# Torsteuerung_1_0.net
KiCad netlist of a schematic drawn in EAGLE
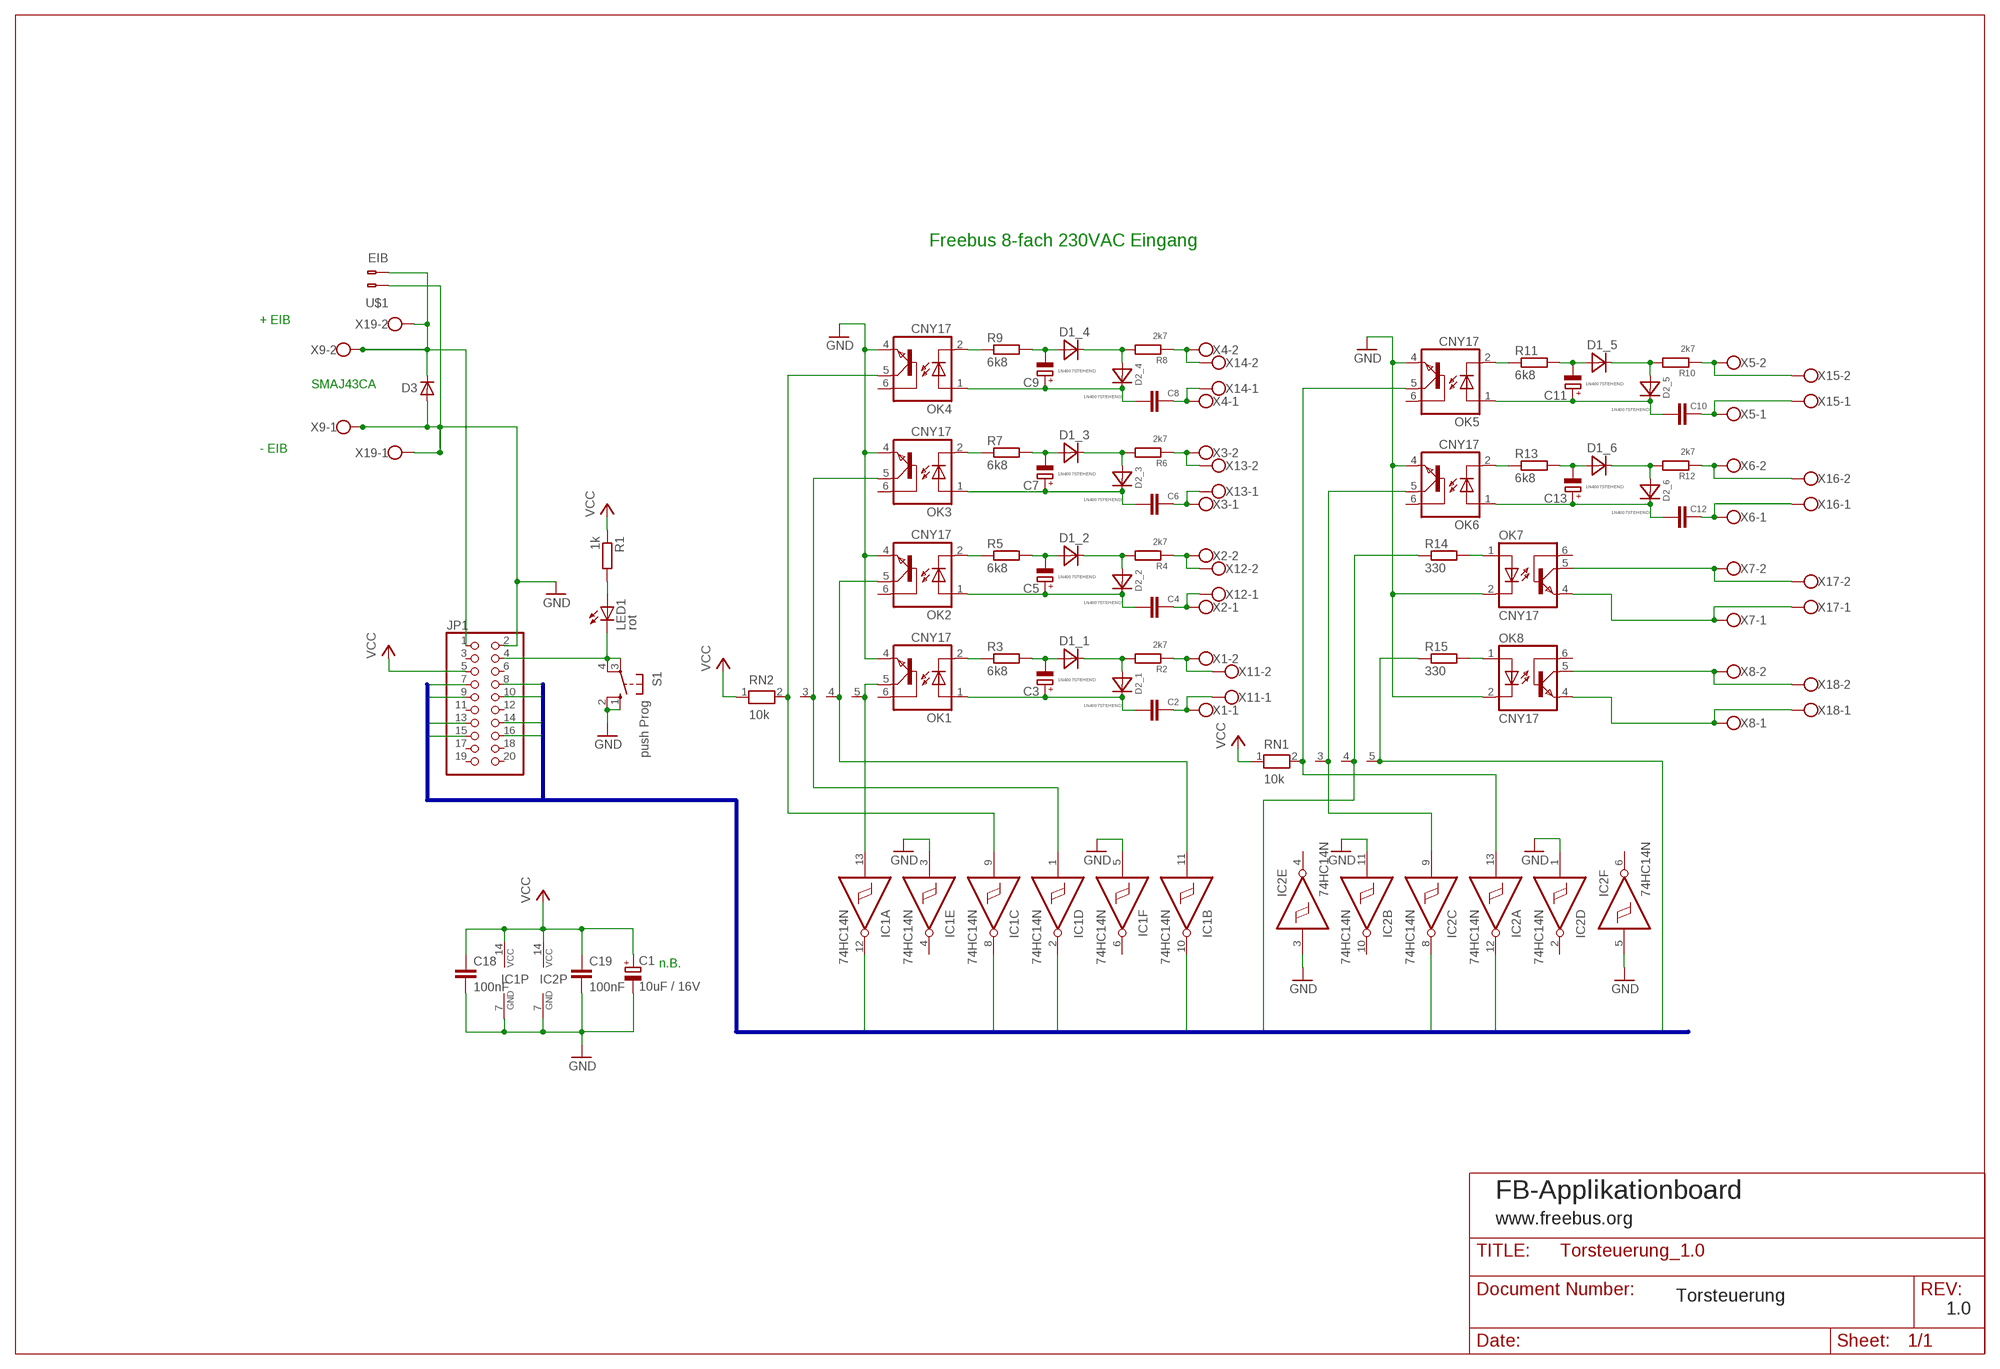
[diagram p0: schematic, sheet 1]

(export (version "E")
  (design (tool "Eeschema 10.0.6"))
  (components
    (comp (ref "C1")
      (value "10uF / 16V")
      (footprint "eagle-import:E2-4")
      (libsource (lib "eagle-import") (part "CPOL-EUE2-4"))
    )
    (comp (ref "C2")
      (value "C-EU075-063X106")
      (footprint "eagle-import:C075-063X106")
      (libsource (lib "eagle-import") (part "C-EU075-063X106"))
    )
    (comp (ref "C3")
      (value "CPOL-EUE2-4")
      (footprint "eagle-import:E2-4")
      (libsource (lib "eagle-import") (part "CPOL-EUE2-4"))
    )
    (comp (ref "C4")
      (value "C-EU075-063X106")
      (footprint "eagle-import:C075-063X106")
      (libsource (lib "eagle-import") (part "C-EU075-063X106"))
    )
    (comp (ref "C5")
      (value "CPOL-EUE2-4")
      (footprint "eagle-import:E2-4")
      (libsource (lib "eagle-import") (part "CPOL-EUE2-4"))
    )
    (comp (ref "C6")
      (value "C-EU075-063X106")
      (footprint "eagle-import:C075-063X106")
      (libsource (lib "eagle-import") (part "C-EU075-063X106"))
    )
    (comp (ref "C7")
      (value "CPOL-EUE2-4")
      (footprint "eagle-import:E2-4")
      (libsource (lib "eagle-import") (part "CPOL-EUE2-4"))
    )
    (comp (ref "C8")
      (value "C-EU075-063X106")
      (footprint "eagle-import:C075-063X106")
      (libsource (lib "eagle-import") (part "C-EU075-063X106"))
    )
    (comp (ref "C9")
      (value "CPOL-EUE2-4")
      (footprint "eagle-import:E2-4")
      (libsource (lib "eagle-import") (part "CPOL-EUE2-4"))
    )
    (comp (ref "C10")
      (value "C-EU075-063X106")
      (footprint "eagle-import:C075-063X106")
      (libsource (lib "eagle-import") (part "C-EU075-063X106"))
    )
    (comp (ref "C11")
      (value "CPOL-EUE2-4")
      (footprint "eagle-import:E2-4")
      (libsource (lib "eagle-import") (part "CPOL-EUE2-4"))
    )
    (comp (ref "C12")
      (value "C-EU075-063X106")
      (footprint "eagle-import:C075-063X106")
      (libsource (lib "eagle-import") (part "C-EU075-063X106"))
    )
    (comp (ref "C13")
      (value "CPOL-EUE2-4")
      (footprint "eagle-import:E2-4")
      (libsource (lib "eagle-import") (part "CPOL-EUE2-4"))
    )
    (comp (ref "C18")
      (value "100nF")
      (footprint "eagle-import:C050-024X044")
      (libsource (lib "eagle-import") (part "C-EU050-024X044"))
    )
    (comp (ref "C19")
      (value "100nF")
      (footprint "eagle-import:C050-024X044")
      (libsource (lib "eagle-import") (part "C-EU050-024X044"))
    )
    (comp (ref "D1_1")
      (value "1N4007STEHEND")
      (footprint "eagle-import:RAD2,5")
      (libsource (lib "eagle-import") (part "1N4007STEHEND"))
    )
    (comp (ref "D1_2")
      (value "1N4007STEHEND")
      (footprint "eagle-import:RAD2,5")
      (libsource (lib "eagle-import") (part "1N4007STEHEND"))
    )
    (comp (ref "D1_3")
      (value "1N4007STEHEND")
      (footprint "eagle-import:RAD2,5")
      (libsource (lib "eagle-import") (part "1N4007STEHEND"))
    )
    (comp (ref "D1_4")
      (value "1N4007STEHEND")
      (footprint "eagle-import:RAD2,5")
      (libsource (lib "eagle-import") (part "1N4007STEHEND"))
    )
    (comp (ref "D1_5")
      (value "1N4007STEHEND")
      (footprint "eagle-import:RAD2,5")
      (libsource (lib "eagle-import") (part "1N4007STEHEND"))
    )
    (comp (ref "D1_6")
      (value "1N4007STEHEND")
      (footprint "eagle-import:RAD2,5")
      (libsource (lib "eagle-import") (part "1N4007STEHEND"))
    )
    (comp (ref "D2_1")
      (value "1N4007STEHEND")
      (footprint "eagle-import:RAD2,5")
      (libsource (lib "eagle-import") (part "1N4007STEHEND"))
    )
    (comp (ref "D2_2")
      (value "1N4007STEHEND")
      (footprint "eagle-import:RAD2,5")
      (libsource (lib "eagle-import") (part "1N4007STEHEND"))
    )
    (comp (ref "D2_3")
      (value "1N4007STEHEND")
      (footprint "eagle-import:RAD2,5")
      (libsource (lib "eagle-import") (part "1N4007STEHEND"))
    )
    (comp (ref "D2_4")
      (value "1N4007STEHEND")
      (footprint "eagle-import:RAD2,5")
      (libsource (lib "eagle-import") (part "1N4007STEHEND"))
    )
    (comp (ref "D2_5")
      (value "1N4007STEHEND")
      (footprint "eagle-import:RAD2,5")
      (libsource (lib "eagle-import") (part "1N4007STEHEND"))
    )
    (comp (ref "D2_6")
      (value "1N4007STEHEND")
      (footprint "eagle-import:RAD2,5")
      (libsource (lib "eagle-import") (part "1N4007STEHEND"))
    )
    (comp (ref "D3")
      (value "D-SMB")
      (footprint "eagle-import:SMB")
      (libsource (lib "eagle-import") (part "D-SMB"))
    )
    (comp (ref "IC1")
      (value "74HC14N")
      (footprint "eagle-import:DIL14")
      (libsource (lib "eagle-import") (part "7414NHC"))
    )
    (comp (ref "IC2")
      (value "74HC14N")
      (footprint "eagle-import:DIL14")
      (libsource (lib "eagle-import") (part "7414NHC"))
    )
    (comp (ref "JP1")
      (value "PINHD-2X10")
      (footprint "eagle-import:2X10")
      (libsource (lib "eagle-import") (part "PINHD-2X10"))
    )
    (comp (ref "LED1")
      (value "rot")
      (footprint "eagle-import:LED3MM")
      (libsource (lib "eagle-import") (part "LED3MM"))
    )
    (comp (ref "OK1")
      (value "CNY17")
      (footprint "eagle-import:DIL06")
      (libsource (lib "eagle-import") (part "CNY17"))
    )
    (comp (ref "OK2")
      (value "CNY17")
      (footprint "eagle-import:DIL06")
      (libsource (lib "eagle-import") (part "CNY17"))
    )
    (comp (ref "OK3")
      (value "CNY17")
      (footprint "eagle-import:DIL06")
      (libsource (lib "eagle-import") (part "CNY17"))
    )
    (comp (ref "OK4")
      (value "CNY17")
      (footprint "eagle-import:DIL06")
      (libsource (lib "eagle-import") (part "CNY17"))
    )
    (comp (ref "OK5")
      (value "CNY17")
      (footprint "eagle-import:DIL06")
      (libsource (lib "eagle-import") (part "CNY17"))
    )
    (comp (ref "OK6")
      (value "CNY17")
      (footprint "eagle-import:DIL06")
      (libsource (lib "eagle-import") (part "CNY17"))
    )
    (comp (ref "OK7")
      (value "CNY17")
      (footprint "eagle-import:DIL06")
      (libsource (lib "eagle-import") (part "CNY17"))
    )
    (comp (ref "OK8")
      (value "CNY17")
      (footprint "eagle-import:DIL06")
      (libsource (lib "eagle-import") (part "CNY17"))
    )
    (comp (ref "R1")
      (value "1k")
      (footprint "eagle-import:0204_7")
      (libsource (lib "eagle-import") (part "R-EU_0204/7"))
    )
    (comp (ref "R2")
      (value "2k7")
      (footprint "eagle-import:0207_2V")
      (libsource (lib "eagle-import") (part "R-EU_0207/2V"))
    )
    (comp (ref "R3")
      (value "6k8")
      (footprint "eagle-import:0207_2V")
      (libsource (lib "eagle-import") (part "R-EU_0207/2V"))
    )
    (comp (ref "R4")
      (value "2k7")
      (footprint "eagle-import:0207_2V")
      (libsource (lib "eagle-import") (part "R-EU_0207/2V"))
    )
    (comp (ref "R5")
      (value "6k8")
      (footprint "eagle-import:0207_2V")
      (libsource (lib "eagle-import") (part "R-EU_0207/2V"))
    )
    (comp (ref "R6")
      (value "2k7")
      (footprint "eagle-import:0207_2V")
      (libsource (lib "eagle-import") (part "R-EU_0207/2V"))
    )
    (comp (ref "R7")
      (value "6k8")
      (footprint "eagle-import:0207_2V")
      (libsource (lib "eagle-import") (part "R-EU_0207/2V"))
    )
    (comp (ref "R8")
      (value "2k7")
      (footprint "eagle-import:0207_2V")
      (libsource (lib "eagle-import") (part "R-EU_0207/2V"))
    )
    (comp (ref "R9")
      (value "6k8")
      (footprint "eagle-import:0207_2V")
      (libsource (lib "eagle-import") (part "R-EU_0207/2V"))
    )
    (comp (ref "R10")
      (value "2k7")
      (footprint "eagle-import:0207_2V")
      (libsource (lib "eagle-import") (part "R-EU_0207/2V"))
    )
    (comp (ref "R11")
      (value "6k8")
      (footprint "eagle-import:0207_2V")
      (libsource (lib "eagle-import") (part "R-EU_0207/2V"))
    )
    (comp (ref "R12")
      (value "2k7")
      (footprint "eagle-import:0207_2V")
      (libsource (lib "eagle-import") (part "R-EU_0207/2V"))
    )
    (comp (ref "R13")
      (value "6k8")
      (footprint "eagle-import:0207_2V")
      (libsource (lib "eagle-import") (part "R-EU_0207/2V"))
    )
    (comp (ref "R14")
      (value "330")
      (footprint "eagle-import:0204_5")
      (libsource (lib "eagle-import") (part "R-EU_0204/5"))
    )
    (comp (ref "R15")
      (value "330")
      (footprint "eagle-import:0204_5")
      (libsource (lib "eagle-import") (part "R-EU_0204/5"))
    )
    (comp (ref "RN1")
      (value "10k")
      (footprint "eagle-import:RN-5")
      (libsource (lib "eagle-import") (part "RN04"))
    )
    (comp (ref "RN2")
      (value "10k")
      (footprint "eagle-import:RN-5")
      (libsource (lib "eagle-import") (part "RN04"))
    )
    (comp (ref "S1")
      (value "push Prog")
      (footprint "eagle-import:B3F-10XX")
      (libsource (lib "eagle-import") (part "10-XX"))
    )
    (comp (ref "U$1")
      (value "EIB")
      (footprint "eagle-import:BUSKLEMME243-724")
      (libsource (lib "eagle-import") (part "EIB"))
    )
    (comp (ref "X1")
      (value "W237-102")
      (footprint "eagle-import:W237-102")
      (libsource (lib "eagle-import") (part "W237-102"))
    )
    (comp (ref "X2")
      (value "W237-102")
      (footprint "eagle-import:W237-102")
      (libsource (lib "eagle-import") (part "W237-102"))
    )
    (comp (ref "X3")
      (value "W237-102")
      (footprint "eagle-import:W237-102")
      (libsource (lib "eagle-import") (part "W237-102"))
    )
    (comp (ref "X4")
      (value "W237-102")
      (footprint "eagle-import:W237-102")
      (libsource (lib "eagle-import") (part "W237-102"))
    )
    (comp (ref "X5")
      (value "W237-102")
      (footprint "eagle-import:W237-102")
      (libsource (lib "eagle-import") (part "W237-102"))
    )
    (comp (ref "X6")
      (value "W237-102")
      (footprint "eagle-import:W237-102")
      (libsource (lib "eagle-import") (part "W237-102"))
    )
    (comp (ref "X7")
      (value "W237-102")
      (footprint "eagle-import:W237-102")
      (libsource (lib "eagle-import") (part "W237-102"))
    )
    (comp (ref "X8")
      (value "W237-102")
      (footprint "eagle-import:W237-102")
      (libsource (lib "eagle-import") (part "W237-102"))
    )
    (comp (ref "X9")
      (value "W237-102")
      (footprint "eagle-import:W237-102")
      (libsource (lib "eagle-import") (part "W237-102"))
    )
    (comp (ref "X11")
      (value "W237-102AKL007-2P")
      (footprint "eagle-import:AKL007-02")
      (libsource (lib "eagle-import") (part "W237-102AKL007-2P"))
    )
    (comp (ref "X12")
      (value "W237-102AKL007-2P")
      (footprint "eagle-import:AKL007-02")
      (libsource (lib "eagle-import") (part "W237-102AKL007-2P"))
    )
    (comp (ref "X13")
      (value "W237-102AKL007-2P")
      (footprint "eagle-import:AKL007-02")
      (libsource (lib "eagle-import") (part "W237-102AKL007-2P"))
    )
    (comp (ref "X14")
      (value "W237-102AKL007-2P")
      (footprint "eagle-import:AKL007-02")
      (libsource (lib "eagle-import") (part "W237-102AKL007-2P"))
    )
    (comp (ref "X15")
      (value "W237-102AKL007-2P")
      (footprint "eagle-import:AKL007-02")
      (libsource (lib "eagle-import") (part "W237-102AKL007-2P"))
    )
    (comp (ref "X16")
      (value "W237-102AKL007-2P")
      (footprint "eagle-import:AKL007-02")
      (libsource (lib "eagle-import") (part "W237-102AKL007-2P"))
    )
    (comp (ref "X17")
      (value "W237-102AKL007-2P")
      (footprint "eagle-import:AKL007-02")
      (libsource (lib "eagle-import") (part "W237-102AKL007-2P"))
    )
    (comp (ref "X18")
      (value "W237-102AKL007-2P")
      (footprint "eagle-import:AKL007-02")
      (libsource (lib "eagle-import") (part "W237-102AKL007-2P"))
    )
    (comp (ref "X19")
      (value "W237-102AKL007-2P")
      (footprint "eagle-import:AKL007-02")
      (libsource (lib "eagle-import") (part "W237-102AKL007-2P"))
    )
  )
  (nets
    (net (code "1") (name "/IO1") (class "Default")
      (node (ref "IC1") (pin "12") (pinfunction "O_12") (pintype "output"))
      (node (ref "JP1") (pin "7") (pinfunction "7_7") (pintype "passive"))
    )
    (net (code "2") (name "/IO2") (class "Default")
      (node (ref "IC1") (pin "10") (pinfunction "O_10") (pintype "output"))
      (node (ref "JP1") (pin "8") (pinfunction "8_8") (pintype "passive"))
    )
    (net (code "3") (name "/IO3") (class "Default")
      (node (ref "IC1") (pin "2") (pinfunction "O_2") (pintype "output"))
      (node (ref "JP1") (pin "9") (pinfunction "9_9") (pintype "passive"))
    )
    (net (code "4") (name "/IO4") (class "Default")
      (node (ref "IC1") (pin "8") (pinfunction "O_8") (pintype "output"))
      (node (ref "JP1") (pin "10") (pinfunction "10_10") (pintype "passive"))
    )
    (net (code "5") (name "/IO5") (class "Default")
      (node (ref "IC2") (pin "12") (pinfunction "O_12") (pintype "output"))
      (node (ref "JP1") (pin "13") (pinfunction "13_13") (pintype "passive"))
    )
    (net (code "6") (name "/IO6") (class "Default")
      (node (ref "IC2") (pin "8") (pinfunction "O_8") (pintype "output"))
      (node (ref "JP1") (pin "14") (pinfunction "14_14") (pintype "passive"))
    )
    (net (code "7") (name "/IO7") (class "Default")
      (node (ref "JP1") (pin "15") (pinfunction "15_15") (pintype "passive"))
      (node (ref "R14") (pin "1") (pinfunction "1_1") (pintype "passive"))
      (node (ref "RN1") (pin "4") (pinfunction "4_4") (pintype "passive"))
    )
    (net (code "8") (name "/IO8") (class "Default")
      (node (ref "JP1") (pin "16") (pinfunction "16_16") (pintype "passive"))
      (node (ref "R15") (pin "1") (pinfunction "1_1") (pintype "passive"))
      (node (ref "RN1") (pin "5") (pinfunction "5_5") (pintype "passive"))
    )
    (net (code "9") (name "GND") (class "Default")
      (node (ref "C1") (pin "-") (pinfunction "-_-") (pintype "passive"))
      (node (ref "C18") (pin "2") (pinfunction "2_2") (pintype "passive"))
      (node (ref "C19") (pin "2") (pinfunction "2_2") (pintype "passive"))
      (node (ref "D3") (pin "2") (pinfunction "A_2") (pintype "passive"))
      (node (ref "IC1") (pin "3") (pinfunction "I_3") (pintype "input"))
      (node (ref "IC1") (pin "5") (pinfunction "I_5") (pintype "input"))
      (node (ref "IC1") (pin "7") (pinfunction "GND_7") (pintype "power_in"))
      (node (ref "IC2") (pin "1") (pinfunction "I_1") (pintype "input"))
      (node (ref "IC2") (pin "11") (pinfunction "I_11") (pintype "input"))
      (node (ref "IC2") (pin "3") (pinfunction "I_3") (pintype "input"))
      (node (ref "IC2") (pin "5") (pinfunction "I_5") (pintype "input"))
      (node (ref "IC2") (pin "7") (pinfunction "GND_7") (pintype "power_in"))
      (node (ref "JP1") (pin "2") (pinfunction "2_2") (pintype "passive"))
      (node (ref "OK1") (pin "4") (pinfunction "EMI_4") (pintype "passive"))
      (node (ref "OK2") (pin "4") (pinfunction "EMI_4") (pintype "passive"))
      (node (ref "OK3") (pin "4") (pinfunction "EMI_4") (pintype "passive"))
      (node (ref "OK4") (pin "4") (pinfunction "EMI_4") (pintype "passive"))
      (node (ref "OK5") (pin "4") (pinfunction "EMI_4") (pintype "passive"))
      (node (ref "OK6") (pin "4") (pinfunction "EMI_4") (pintype "passive"))
      (node (ref "OK7") (pin "2") (pinfunction "C_2") (pintype "passive"))
      (node (ref "OK8") (pin "2") (pinfunction "C_2") (pintype "passive"))
      (node (ref "S1") (pin "1") (pinfunction "S_1") (pintype "passive"))
      (node (ref "S1") (pin "2") (pinfunction "S1_2") (pintype "passive"))
      (node (ref "U$1") (pin "1") (pinfunction "B-1_1") (pintype "passive"))
      (node (ref "X19") (pin "1") (pinfunction "KL_1") (pintype "passive"))
      (node (ref "X9") (pin "1") (pinfunction "KL_1") (pintype "passive"))
    )
    (net (code "10") (name "Net-(C3-Pad-)") (class "Default")
      (node (ref "C3") (pin "-") (pinfunction "-_-") (pintype "passive"))
      (node (ref "D1_1") (pin "A") (pinfunction "A_A") (pintype "passive"))
      (node (ref "R3") (pin "2") (pinfunction "2_2") (pintype "passive"))
    )
    (net (code "11") (name "Net-(C5-Pad-)") (class "Default")
      (node (ref "C5") (pin "-") (pinfunction "-_-") (pintype "passive"))
      (node (ref "D1_2") (pin "A") (pinfunction "A_A") (pintype "passive"))
      (node (ref "R5") (pin "2") (pinfunction "2_2") (pintype "passive"))
    )
    (net (code "12") (name "Net-(C7-Pad-)") (class "Default")
      (node (ref "C7") (pin "-") (pinfunction "-_-") (pintype "passive"))
      (node (ref "D1_3") (pin "A") (pinfunction "A_A") (pintype "passive"))
      (node (ref "R7") (pin "2") (pinfunction "2_2") (pintype "passive"))
    )
    (net (code "13") (name "Net-(C9-Pad-)") (class "Default")
      (node (ref "C9") (pin "-") (pinfunction "-_-") (pintype "passive"))
      (node (ref "D1_4") (pin "A") (pinfunction "A_A") (pintype "passive"))
      (node (ref "R9") (pin "2") (pinfunction "2_2") (pintype "passive"))
    )
    (net (code "14") (name "Net-(C11-Pad-)") (class "Default")
      (node (ref "C11") (pin "-") (pinfunction "-_-") (pintype "passive"))
      (node (ref "D1_5") (pin "A") (pinfunction "A_A") (pintype "passive"))
      (node (ref "R11") (pin "2") (pinfunction "2_2") (pintype "passive"))
    )
    (net (code "15") (name "Net-(C13-Pad-)") (class "Default")
      (node (ref "C13") (pin "-") (pinfunction "-_-") (pintype "passive"))
      (node (ref "D1_6") (pin "A") (pinfunction "A_A") (pintype "passive"))
      (node (ref "R13") (pin "2") (pinfunction "2_2") (pintype "passive"))
    )
    (net (code "16") (name "Net-(D1_1-PadC)") (class "Default")
      (node (ref "D1_1") (pin "C") (pinfunction "C_C") (pintype "passive"))
      (node (ref "D2_1") (pin "A") (pinfunction "A_A") (pintype "passive"))
      (node (ref "R2") (pin "2") (pinfunction "2_2") (pintype "passive"))
    )
    (net (code "17") (name "Net-(D1_2-PadC)") (class "Default")
      (node (ref "D1_2") (pin "C") (pinfunction "C_C") (pintype "passive"))
      (node (ref "D2_2") (pin "A") (pinfunction "A_A") (pintype "passive"))
      (node (ref "R4") (pin "2") (pinfunction "2_2") (pintype "passive"))
    )
    (net (code "18") (name "Net-(D1_3-PadC)") (class "Default")
      (node (ref "D1_3") (pin "C") (pinfunction "C_C") (pintype "passive"))
      (node (ref "D2_3") (pin "A") (pinfunction "A_A") (pintype "passive"))
      (node (ref "R6") (pin "2") (pinfunction "2_2") (pintype "passive"))
    )
    (net (code "19") (name "Net-(D1_4-PadC)") (class "Default")
      (node (ref "D1_4") (pin "C") (pinfunction "C_C") (pintype "passive"))
      (node (ref "D2_4") (pin "A") (pinfunction "A_A") (pintype "passive"))
      (node (ref "R8") (pin "2") (pinfunction "2_2") (pintype "passive"))
    )
    (net (code "20") (name "Net-(D1_5-PadC)") (class "Default")
      (node (ref "D1_5") (pin "C") (pinfunction "C_C") (pintype "passive"))
      (node (ref "D2_5") (pin "A") (pinfunction "A_A") (pintype "passive"))
      (node (ref "R10") (pin "2") (pinfunction "2_2") (pintype "passive"))
    )
    (net (code "21") (name "Net-(D1_6-PadC)") (class "Default")
      (node (ref "D1_6") (pin "C") (pinfunction "C_C") (pintype "passive"))
      (node (ref "D2_6") (pin "A") (pinfunction "A_A") (pintype "passive"))
      (node (ref "R12") (pin "2") (pinfunction "2_2") (pintype "passive"))
    )
    (net (code "22") (name "Net-(D3-C)") (class "Default")
      (node (ref "D3") (pin "1") (pinfunction "C_1") (pintype "passive"))
      (node (ref "JP1") (pin "1") (pinfunction "1_1") (pintype "passive"))
      (node (ref "U$1") (pin "2") (pinfunction "B-2_2") (pintype "passive"))
      (node (ref "X19") (pin "2") (pinfunction "KL_2") (pintype "passive"))
      (node (ref "X9") (pin "2") (pinfunction "KL_2") (pintype "passive"))
    )
    (net (code "23") (name "Net-(IC1A-I)") (class "Default")
      (node (ref "IC1") (pin "13") (pinfunction "I_13") (pintype "input"))
      (node (ref "OK1") (pin "5") (pinfunction "COL_5") (pintype "passive"))
      (node (ref "RN2") (pin "5") (pinfunction "5_5") (pintype "passive"))
    )
    (net (code "24") (name "Net-(IC1B-I)") (class "Default")
      (node (ref "IC1") (pin "11") (pinfunction "I_11") (pintype "input"))
      (node (ref "OK2") (pin "5") (pinfunction "COL_5") (pintype "passive"))
      (node (ref "RN2") (pin "4") (pinfunction "4_4") (pintype "passive"))
    )
    (net (code "25") (name "Net-(IC1C-I)") (class "Default")
      (node (ref "IC1") (pin "9") (pinfunction "I_9") (pintype "input"))
      (node (ref "OK4") (pin "5") (pinfunction "COL_5") (pintype "passive"))
      (node (ref "RN2") (pin "2") (pinfunction "2_2") (pintype "passive"))
    )
    (net (code "26") (name "Net-(IC1D-I)") (class "Default")
      (node (ref "IC1") (pin "1") (pinfunction "I_1") (pintype "input"))
      (node (ref "OK3") (pin "5") (pinfunction "COL_5") (pintype "passive"))
      (node (ref "RN2") (pin "3") (pinfunction "3_3") (pintype "passive"))
    )
    (net (code "27") (name "Net-(IC2A-I)") (class "Default")
      (node (ref "IC2") (pin "13") (pinfunction "I_13") (pintype "input"))
      (node (ref "OK5") (pin "5") (pinfunction "COL_5") (pintype "passive"))
      (node (ref "RN1") (pin "2") (pinfunction "2_2") (pintype "passive"))
    )
    (net (code "28") (name "Net-(IC2C-I)") (class "Default")
      (node (ref "IC2") (pin "9") (pinfunction "I_9") (pintype "input"))
      (node (ref "OK6") (pin "5") (pinfunction "COL_5") (pintype "passive"))
      (node (ref "RN1") (pin "3") (pinfunction "3_3") (pintype "passive"))
    )
    (net (code "29") (name "Net-(LED1-C)") (class "Default")
      (node (ref "JP1") (pin "4") (pinfunction "4_4") (pintype "passive"))
      (node (ref "LED1") (pin "K") (pinfunction "C_K") (pintype "passive"))
      (node (ref "S1") (pin "3") (pinfunction "P_3") (pintype "passive"))
      (node (ref "S1") (pin "4") (pinfunction "P1_4") (pintype "passive"))
    )
    (net (code "30") (name "Net-(LED1-PadA)") (class "Default")
      (node (ref "LED1") (pin "A") (pinfunction "A_A") (pintype "passive"))
      (node (ref "R1") (pin "2") (pinfunction "2_2") (pintype "passive"))
    )
    (net (code "31") (name "Net-(OK1-A)") (class "Default")
      (node (ref "C2") (pin "1") (pinfunction "1_1") (pintype "passive"))
      (node (ref "C3") (pin "+") (pinfunction "+_+") (pintype "passive"))
      (node (ref "D2_1") (pin "C") (pinfunction "C_C") (pintype "passive"))
      (node (ref "OK1") (pin "1") (pinfunction "A_1") (pintype "passive"))
    )
    (net (code "32") (name "Net-(OK1-C)") (class "Default")
      (node (ref "OK1") (pin "2") (pinfunction "C_2") (pintype "passive"))
      (node (ref "R3") (pin "1") (pinfunction "1_1") (pintype "passive"))
    )
    (net (code "33") (name "Net-(OK2-A)") (class "Default")
      (node (ref "C4") (pin "1") (pinfunction "1_1") (pintype "passive"))
      (node (ref "C5") (pin "+") (pinfunction "+_+") (pintype "passive"))
      (node (ref "D2_2") (pin "C") (pinfunction "C_C") (pintype "passive"))
      (node (ref "OK2") (pin "1") (pinfunction "A_1") (pintype "passive"))
    )
    (net (code "34") (name "Net-(OK2-C)") (class "Default")
      (node (ref "OK2") (pin "2") (pinfunction "C_2") (pintype "passive"))
      (node (ref "R5") (pin "1") (pinfunction "1_1") (pintype "passive"))
    )
    (net (code "35") (name "Net-(OK3-A)") (class "Default")
      (node (ref "C6") (pin "1") (pinfunction "1_1") (pintype "passive"))
      (node (ref "C7") (pin "+") (pinfunction "+_+") (pintype "passive"))
      (node (ref "D2_3") (pin "C") (pinfunction "C_C") (pintype "passive"))
      (node (ref "OK3") (pin "1") (pinfunction "A_1") (pintype "passive"))
    )
    (net (code "36") (name "Net-(OK3-C)") (class "Default")
      (node (ref "OK3") (pin "2") (pinfunction "C_2") (pintype "passive"))
      (node (ref "R7") (pin "1") (pinfunction "1_1") (pintype "passive"))
    )
    (net (code "37") (name "Net-(OK4-A)") (class "Default")
      (node (ref "C8") (pin "1") (pinfunction "1_1") (pintype "passive"))
      (node (ref "C9") (pin "+") (pinfunction "+_+") (pintype "passive"))
      (node (ref "D2_4") (pin "C") (pinfunction "C_C") (pintype "passive"))
      (node (ref "OK4") (pin "1") (pinfunction "A_1") (pintype "passive"))
    )
    (net (code "38") (name "Net-(OK4-C)") (class "Default")
      (node (ref "OK4") (pin "2") (pinfunction "C_2") (pintype "passive"))
      (node (ref "R9") (pin "1") (pinfunction "1_1") (pintype "passive"))
    )
    (net (code "39") (name "Net-(OK5-A)") (class "Default")
      (node (ref "C10") (pin "1") (pinfunction "1_1") (pintype "passive"))
      (node (ref "C11") (pin "+") (pinfunction "+_+") (pintype "passive"))
      (node (ref "D2_5") (pin "C") (pinfunction "C_C") (pintype "passive"))
      (node (ref "OK5") (pin "1") (pinfunction "A_1") (pintype "passive"))
    )
    (net (code "40") (name "Net-(OK5-C)") (class "Default")
      (node (ref "OK5") (pin "2") (pinfunction "C_2") (pintype "passive"))
      (node (ref "R11") (pin "1") (pinfunction "1_1") (pintype "passive"))
    )
    (net (code "41") (name "Net-(OK6-A)") (class "Default")
      (node (ref "C12") (pin "1") (pinfunction "1_1") (pintype "passive"))
      (node (ref "C13") (pin "+") (pinfunction "+_+") (pintype "passive"))
      (node (ref "D2_6") (pin "C") (pinfunction "C_C") (pintype "passive"))
      (node (ref "OK6") (pin "1") (pinfunction "A_1") (pintype "passive"))
    )
    (net (code "42") (name "Net-(OK6-C)") (class "Default")
      (node (ref "OK6") (pin "2") (pinfunction "C_2") (pintype "passive"))
      (node (ref "R13") (pin "1") (pinfunction "1_1") (pintype "passive"))
    )
    (net (code "43") (name "Net-(OK7-A)") (class "Default")
      (node (ref "OK7") (pin "1") (pinfunction "A_1") (pintype "passive"))
      (node (ref "R14") (pin "2") (pinfunction "2_2") (pintype "passive"))
    )
    (net (code "44") (name "Net-(OK7-COL)") (class "Default")
      (node (ref "OK7") (pin "5") (pinfunction "COL_5") (pintype "passive"))
      (node (ref "X17") (pin "2") (pinfunction "KL_2") (pintype "passive"))
      (node (ref "X7") (pin "2") (pinfunction "KL_2") (pintype "passive"))
    )
    (net (code "45") (name "Net-(OK7-EMI)") (class "Default")
      (node (ref "OK7") (pin "4") (pinfunction "EMI_4") (pintype "passive"))
      (node (ref "X17") (pin "1") (pinfunction "KL_1") (pintype "passive"))
      (node (ref "X7") (pin "1") (pinfunction "KL_1") (pintype "passive"))
    )
    (net (code "46") (name "Net-(OK8-A)") (class "Default")
      (node (ref "OK8") (pin "1") (pinfunction "A_1") (pintype "passive"))
      (node (ref "R15") (pin "2") (pinfunction "2_2") (pintype "passive"))
    )
    (net (code "47") (name "Net-(OK8-COL)") (class "Default")
      (node (ref "OK8") (pin "5") (pinfunction "COL_5") (pintype "passive"))
      (node (ref "X18") (pin "2") (pinfunction "KL_2") (pintype "passive"))
      (node (ref "X8") (pin "2") (pinfunction "KL_2") (pintype "passive"))
    )
    (net (code "48") (name "Net-(OK8-EMI)") (class "Default")
      (node (ref "OK8") (pin "4") (pinfunction "EMI_4") (pintype "passive"))
      (node (ref "X18") (pin "1") (pinfunction "KL_1") (pintype "passive"))
      (node (ref "X8") (pin "1") (pinfunction "KL_1") (pintype "passive"))
    )
    (net (code "49") (name "Net-(X11A-KL)") (class "Default")
      (node (ref "C2") (pin "2") (pinfunction "2_2") (pintype "passive"))
      (node (ref "X1") (pin "1") (pinfunction "KL_1") (pintype "passive"))
      (node (ref "X11") (pin "1") (pinfunction "KL_1") (pintype "passive"))
    )
    (net (code "50") (name "Net-(X11B-KL)") (class "Default")
      (node (ref "R2") (pin "1") (pinfunction "1_1") (pintype "passive"))
      (node (ref "X1") (pin "2") (pinfunction "KL_2") (pintype "passive"))
      (node (ref "X11") (pin "2") (pinfunction "KL_2") (pintype "passive"))
    )
    (net (code "51") (name "Net-(X12A-KL)") (class "Default")
      (node (ref "C4") (pin "2") (pinfunction "2_2") (pintype "passive"))
      (node (ref "X12") (pin "1") (pinfunction "KL_1") (pintype "passive"))
      (node (ref "X2") (pin "1") (pinfunction "KL_1") (pintype "passive"))
    )
    (net (code "52") (name "Net-(X12B-KL)") (class "Default")
      (node (ref "R4") (pin "1") (pinfunction "1_1") (pintype "passive"))
      (node (ref "X12") (pin "2") (pinfunction "KL_2") (pintype "passive"))
      (node (ref "X2") (pin "2") (pinfunction "KL_2") (pintype "passive"))
    )
    (net (code "53") (name "Net-(X13A-KL)") (class "Default")
      (node (ref "C6") (pin "2") (pinfunction "2_2") (pintype "passive"))
      (node (ref "X13") (pin "1") (pinfunction "KL_1") (pintype "passive"))
      (node (ref "X3") (pin "1") (pinfunction "KL_1") (pintype "passive"))
    )
    (net (code "54") (name "Net-(X13B-KL)") (class "Default")
      (node (ref "R6") (pin "1") (pinfunction "1_1") (pintype "passive"))
      (node (ref "X13") (pin "2") (pinfunction "KL_2") (pintype "passive"))
      (node (ref "X3") (pin "2") (pinfunction "KL_2") (pintype "passive"))
    )
    (net (code "55") (name "Net-(X14A-KL)") (class "Default")
      (node (ref "C8") (pin "2") (pinfunction "2_2") (pintype "passive"))
      (node (ref "X14") (pin "1") (pinfunction "KL_1") (pintype "passive"))
      (node (ref "X4") (pin "1") (pinfunction "KL_1") (pintype "passive"))
    )
    (net (code "56") (name "Net-(X14B-KL)") (class "Default")
      (node (ref "R8") (pin "1") (pinfunction "1_1") (pintype "passive"))
      (node (ref "X14") (pin "2") (pinfunction "KL_2") (pintype "passive"))
      (node (ref "X4") (pin "2") (pinfunction "KL_2") (pintype "passive"))
    )
    (net (code "57") (name "Net-(X15A-KL)") (class "Default")
      (node (ref "C10") (pin "2") (pinfunction "2_2") (pintype "passive"))
      (node (ref "X15") (pin "1") (pinfunction "KL_1") (pintype "passive"))
      (node (ref "X5") (pin "1") (pinfunction "KL_1") (pintype "passive"))
    )
    (net (code "58") (name "Net-(X15B-KL)") (class "Default")
      (node (ref "R10") (pin "1") (pinfunction "1_1") (pintype "passive"))
      (node (ref "X15") (pin "2") (pinfunction "KL_2") (pintype "passive"))
      (node (ref "X5") (pin "2") (pinfunction "KL_2") (pintype "passive"))
    )
    (net (code "59") (name "Net-(X16A-KL)") (class "Default")
      (node (ref "C12") (pin "2") (pinfunction "2_2") (pintype "passive"))
      (node (ref "X16") (pin "1") (pinfunction "KL_1") (pintype "passive"))
      (node (ref "X6") (pin "1") (pinfunction "KL_1") (pintype "passive"))
    )
    (net (code "60") (name "Net-(X16B-KL)") (class "Default")
      (node (ref "R12") (pin "1") (pinfunction "1_1") (pintype "passive"))
      (node (ref "X16") (pin "2") (pinfunction "KL_2") (pintype "passive"))
      (node (ref "X6") (pin "2") (pinfunction "KL_2") (pintype "passive"))
    )
    (net (code "61") (name "VCC") (class "Default")
      (node (ref "C1") (pin "+") (pinfunction "+_+") (pintype "passive"))
      (node (ref "C18") (pin "1") (pinfunction "1_1") (pintype "passive"))
      (node (ref "C19") (pin "1") (pinfunction "1_1") (pintype "passive"))
      (node (ref "IC1") (pin "14") (pinfunction "VCC_14") (pintype "power_in"))
      (node (ref "IC2") (pin "14") (pinfunction "VCC_14") (pintype "power_in"))
      (node (ref "JP1") (pin "5") (pinfunction "5_5") (pintype "passive"))
      (node (ref "R1") (pin "1") (pinfunction "1_1") (pintype "passive"))
      (node (ref "RN1") (pin "1") (pinfunction "1_1") (pintype "passive"))
      (node (ref "RN2") (pin "1") (pinfunction "1_1") (pintype "passive"))
    )
    (net (code "62") (name "unconnected-(IC1E-O-Pad4)") (class "Default")
      (node (ref "IC1") (pin "4") (pinfunction "O_4") (pintype "output"))
    )
    (net (code "63") (name "unconnected-(IC1F-O-Pad6)") (class "Default")
      (node (ref "IC1") (pin "6") (pinfunction "O_6") (pintype "output"))
    )
    (net (code "64") (name "unconnected-(IC2B-O-Pad10)") (class "Default")
      (node (ref "IC2") (pin "10") (pinfunction "O_10") (pintype "output"))
    )
    (net (code "65") (name "unconnected-(IC2D-O-Pad2)") (class "Default")
      (node (ref "IC2") (pin "2") (pinfunction "O_2") (pintype "output"))
    )
    (net (code "66") (name "unconnected-(IC2E-O-Pad4)") (class "Default")
      (node (ref "IC2") (pin "4") (pinfunction "O_4") (pintype "output"))
    )
    (net (code "67") (name "unconnected-(IC2F-O-Pad6)") (class "Default")
      (node (ref "IC2") (pin "6") (pinfunction "O_6") (pintype "output"))
    )
    (net (code "68") (name "unconnected-(JP1-Pad3)") (class "Default")
      (node (ref "JP1") (pin "3") (pinfunction "3_3") (pintype "passive"))
    )
    (net (code "69") (name "unconnected-(JP1-Pad6)") (class "Default")
      (node (ref "JP1") (pin "6") (pinfunction "6_6") (pintype "passive"))
    )
    (net (code "70") (name "unconnected-(JP1-Pad11)") (class "Default")
      (node (ref "JP1") (pin "11") (pinfunction "11_11") (pintype "passive"))
    )
    (net (code "71") (name "unconnected-(JP1-Pad12)") (class "Default")
      (node (ref "JP1") (pin "12") (pinfunction "12_12") (pintype "passive"))
    )
    (net (code "72") (name "unconnected-(JP1-Pad17)") (class "Default")
      (node (ref "JP1") (pin "17") (pinfunction "17_17") (pintype "passive"))
    )
    (net (code "73") (name "unconnected-(JP1-Pad18)") (class "Default")
      (node (ref "JP1") (pin "18") (pinfunction "18_18") (pintype "passive"))
    )
    (net (code "74") (name "unconnected-(JP1-Pad19)") (class "Default")
      (node (ref "JP1") (pin "19") (pinfunction "19_19") (pintype "passive"))
    )
    (net (code "75") (name "unconnected-(JP1-Pad20)") (class "Default")
      (node (ref "JP1") (pin "20") (pinfunction "20_20") (pintype "passive"))
    )
    (net (code "76") (name "unconnected-(OK1-BAS-Pad6)") (class "Default")
      (node (ref "OK1") (pin "6") (pinfunction "BAS_6") (pintype "passive"))
    )
    (net (code "77") (name "unconnected-(OK2-BAS-Pad6)") (class "Default")
      (node (ref "OK2") (pin "6") (pinfunction "BAS_6") (pintype "passive"))
    )
    (net (code "78") (name "unconnected-(OK3-BAS-Pad6)") (class "Default")
      (node (ref "OK3") (pin "6") (pinfunction "BAS_6") (pintype "passive"))
    )
    (net (code "79") (name "unconnected-(OK4-BAS-Pad6)") (class "Default")
      (node (ref "OK4") (pin "6") (pinfunction "BAS_6") (pintype "passive"))
    )
    (net (code "80") (name "unconnected-(OK5-BAS-Pad6)") (class "Default")
      (node (ref "OK5") (pin "6") (pinfunction "BAS_6") (pintype "passive"))
    )
    (net (code "81") (name "unconnected-(OK6-BAS-Pad6)") (class "Default")
      (node (ref "OK6") (pin "6") (pinfunction "BAS_6") (pintype "passive"))
    )
    (net (code "82") (name "unconnected-(OK7-BAS-Pad6)") (class "Default")
      (node (ref "OK7") (pin "6") (pinfunction "BAS_6") (pintype "passive"))
    )
    (net (code "83") (name "unconnected-(OK8-BAS-Pad6)") (class "Default")
      (node (ref "OK8") (pin "6") (pinfunction "BAS_6") (pintype "passive"))
    )
  )
)
